# LED_PROJECT.net
KiCad netlist of a schematic drawn in Altium Designer
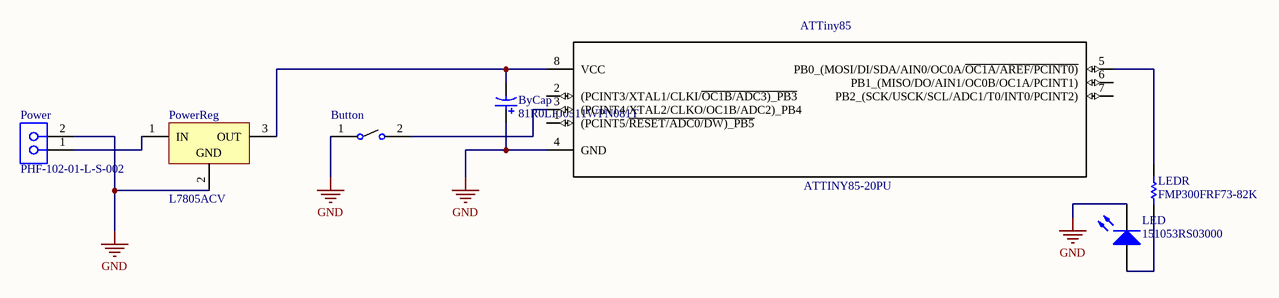
[diagram p0: LED_PROJECT.SchDoc]

(export (version "E")
  (design (tool "Eeschema 10.0.6"))
  (components
    (comp (ref "ATTiny85")
      (value "ATTINY85-20PU")
      (footprint "DIP254P762X533-8")
      (description "ATtiny Series 20 MHz 8 KB Flash 512 B SRAM 8-Bit Microcontroller - DIP-8")
      (fields (field (name "MF") "Microchip"))
      (libsource (lib "ATTINY85-20PU") (part "ATTINY85-20PU"))
    )
    (comp (ref "Button")
      (value "147694-1")
      (footprint "TE_FSM8JRT")
      (description "FSM8JRT=SWITCH,PUSHBUTTON,TACT")
      (fields (field (name "MP") "FSM8JRT") (field (name "DIGI-KEY_PART_NUMBER") "450-2039-1-ND"))
      (libsource (lib "FSM8JRT") (part "FSM8JRT"))
    )
    (comp (ref "ByCap")
      (value "81R0LFJ0511WPN081T")
      (footprint "FHTE-8-0511-2_M")
      (fields
        (field (name "VOLTAGE") "50 V")
        (field (name "MANUFACTURER") "Fenghuang Technology")
        (field (name "TOLERANCE") "+/- 5%")
      )
      (libsource (lib "Altium Content Vault") (part "FHTE-CAP-P-2"))
    )
    (comp (ref "LED")
      (value "151053RS03000")
      (footprint "Type 5mm")
      (description "THT LED round mono-color waterclear,  WL-TMRW ,Red")
      (fields (field (name "MANUFACTURER") "Wuerth Elektronik"))
      (libsource (lib "Altium Content Vault") (part "WE-LED_K1A2-2"))
    )
    (comp (ref "LEDR")
      (value "FMP300FRF73-82K")
      (footprint "YAGO-FMP300-2_V2")
      (description "Metal Film Resistor, 82 KOhm +/-1%, 3 W, -55 to 155 degC, 2-Pin THD, RoHS, Tape and Reel")
      (fields (field (name "MANUFACTURER") "Yageo"))
      (libsource (lib "Altium Content Vault") (part "YAGO-RES-2"))
    )
    (comp (ref "Power")
      (value "PHF-102-01-L-S-002")
      (footprint "SMTC-PHF-102-01-X-S-002")
      (description "Press Fit Socket, Through-hole, Vertical, -55 to 125 degC, 2.54 mm Pitch, 2-Pin, Female, RoHS")
      (fields (field (name "MANUFACTURER") "Samtec"))
      (libsource (lib "Altium Content Vault") (part "SMTC-PHF-102-X-X-S"))
    )
    (comp (ref "PowerReg")
      (value "L7805ACV")
      (footprint "TO220")
      (description "Positive Voltage Regulator, 5V, 3-Pin TO-220")
      (libsource (lib "Altium Content Vault") (part "PM-REG-L4940-SIL3"))
    )
  )
  (nets
    (net (code "1") (name "GND") (class "Default")
      (node (ref "ATTiny85") (pin "4") (pinfunction "GND_4") (pintype "passive"))
      (node (ref "Button") (pin "1") (pinfunction "1_1") (pintype "passive"))
      (node (ref "ByCap") (pin "1") (pinfunction "1_1") (pintype "passive"))
      (node (ref "LED") (pin "1") (pinfunction "K_1") (pintype "passive"))
      (node (ref "Power") (pin "2") (pinfunction "2_2") (pintype "passive"))
      (node (ref "PowerReg") (pin "2") (pinfunction "GND_2") (pintype "power_in"))
    )
    (net (code "2") (name "Net-(ATTiny85-(PCINT4{slash}XTAL2{slash}CLKO{slash}OC1B{slash}ADC2)_PB4)") (class "Default")
      (node (ref "ATTiny85") (pin "3") (pinfunction "(PCINT4/XTAL2/CLKO/OC1B/ADC2)_PB4_3") (pintype "bidirectional"))
      (node (ref "Button") (pin "2") (pinfunction "2_2") (pintype "passive"))
    )
    (net (code "3") (name "Net-(ATTiny85-PB0_(MOSI{slash}DI{slash}SDA{slash}AIN0{slash}OC0A{slash}~{OC1A{slash}AREF{slash}PCINT0)})") (class "Default")
      (node (ref "ATTiny85") (pin "5") (pinfunction "PB0_(MOSI/DI/SDA/AIN0/OC0A/~{OC1A/AREF/PCINT0)}_5") (pintype "bidirectional"))
      (node (ref "LEDR") (pin "2") (pinfunction "2_2") (pintype "passive"))
    )
    (net (code "4") (name "Net-(ATTiny85-VCC)") (class "Default")
      (node (ref "ATTiny85") (pin "8") (pinfunction "VCC_8") (pintype "power_in"))
      (node (ref "ByCap") (pin "2") (pinfunction "2_2") (pintype "passive"))
      (node (ref "PowerReg") (pin "3") (pinfunction "OUT_3") (pintype "power_in"))
    )
    (net (code "5") (name "Net-(LED-A)") (class "Default")
      (node (ref "LED") (pin "2") (pinfunction "A_2") (pintype "passive"))
      (node (ref "LEDR") (pin "1") (pinfunction "1_1") (pintype "passive"))
    )
    (net (code "6") (name "Net-(PowerReg-IN)") (class "Default")
      (node (ref "Power") (pin "1") (pinfunction "1_1") (pintype "passive"))
      (node (ref "PowerReg") (pin "1") (pinfunction "IN_1") (pintype "power_in"))
    )
    (net (code "7") (name "unconnected-(ATTiny85-(PCINT3{slash}XTAL1{slash}CLKI{slash}~{OC1B{slash}ADC3)_PB3}-Pad2)") (class "Default")
      (node (ref "ATTiny85") (pin "2") (pinfunction "(PCINT3/XTAL1/CLKI/~{OC1B/ADC3)_PB3}_2") (pintype "bidirectional"))
    )
    (net (code "8") (name "unconnected-(ATTiny85-(PCINT5{slash}~{RESET{slash}ADC0{slash}DW)_PB5}-Pad1)") (class "Default")
      (node (ref "ATTiny85") (pin "1") (pinfunction "(PCINT5/~{RESET/ADC0/DW)_PB5}_1") (pintype "bidirectional"))
    )
    (net (code "9") (name "unconnected-(ATTiny85-PB1_(MISO{slash}DO{slash}AIN1{slash}OC0B{slash}OC1A{slash}PCINT1)-Pad6)") (class "Default")
      (node (ref "ATTiny85") (pin "6") (pinfunction "PB1_(MISO/DO/AIN1/OC0B/OC1A/PCINT1)_6") (pintype "bidirectional"))
    )
    (net (code "10") (name "unconnected-(ATTiny85-PB2_(SCK{slash}USCK{slash}SCL{slash}ADC1{slash}T0{slash}INT0{slash}PCINT2)-Pad7)") (class "Default")
      (node (ref "ATTiny85") (pin "7") (pinfunction "PB2_(SCK/USCK/SCL/ADC1/T0/INT0/PCINT2)_7") (pintype "bidirectional"))
    )
  )
)
